# ProPrj__B__2024-10-26.net
KiCad netlist of a schematic drawn in EasyEDA Pro
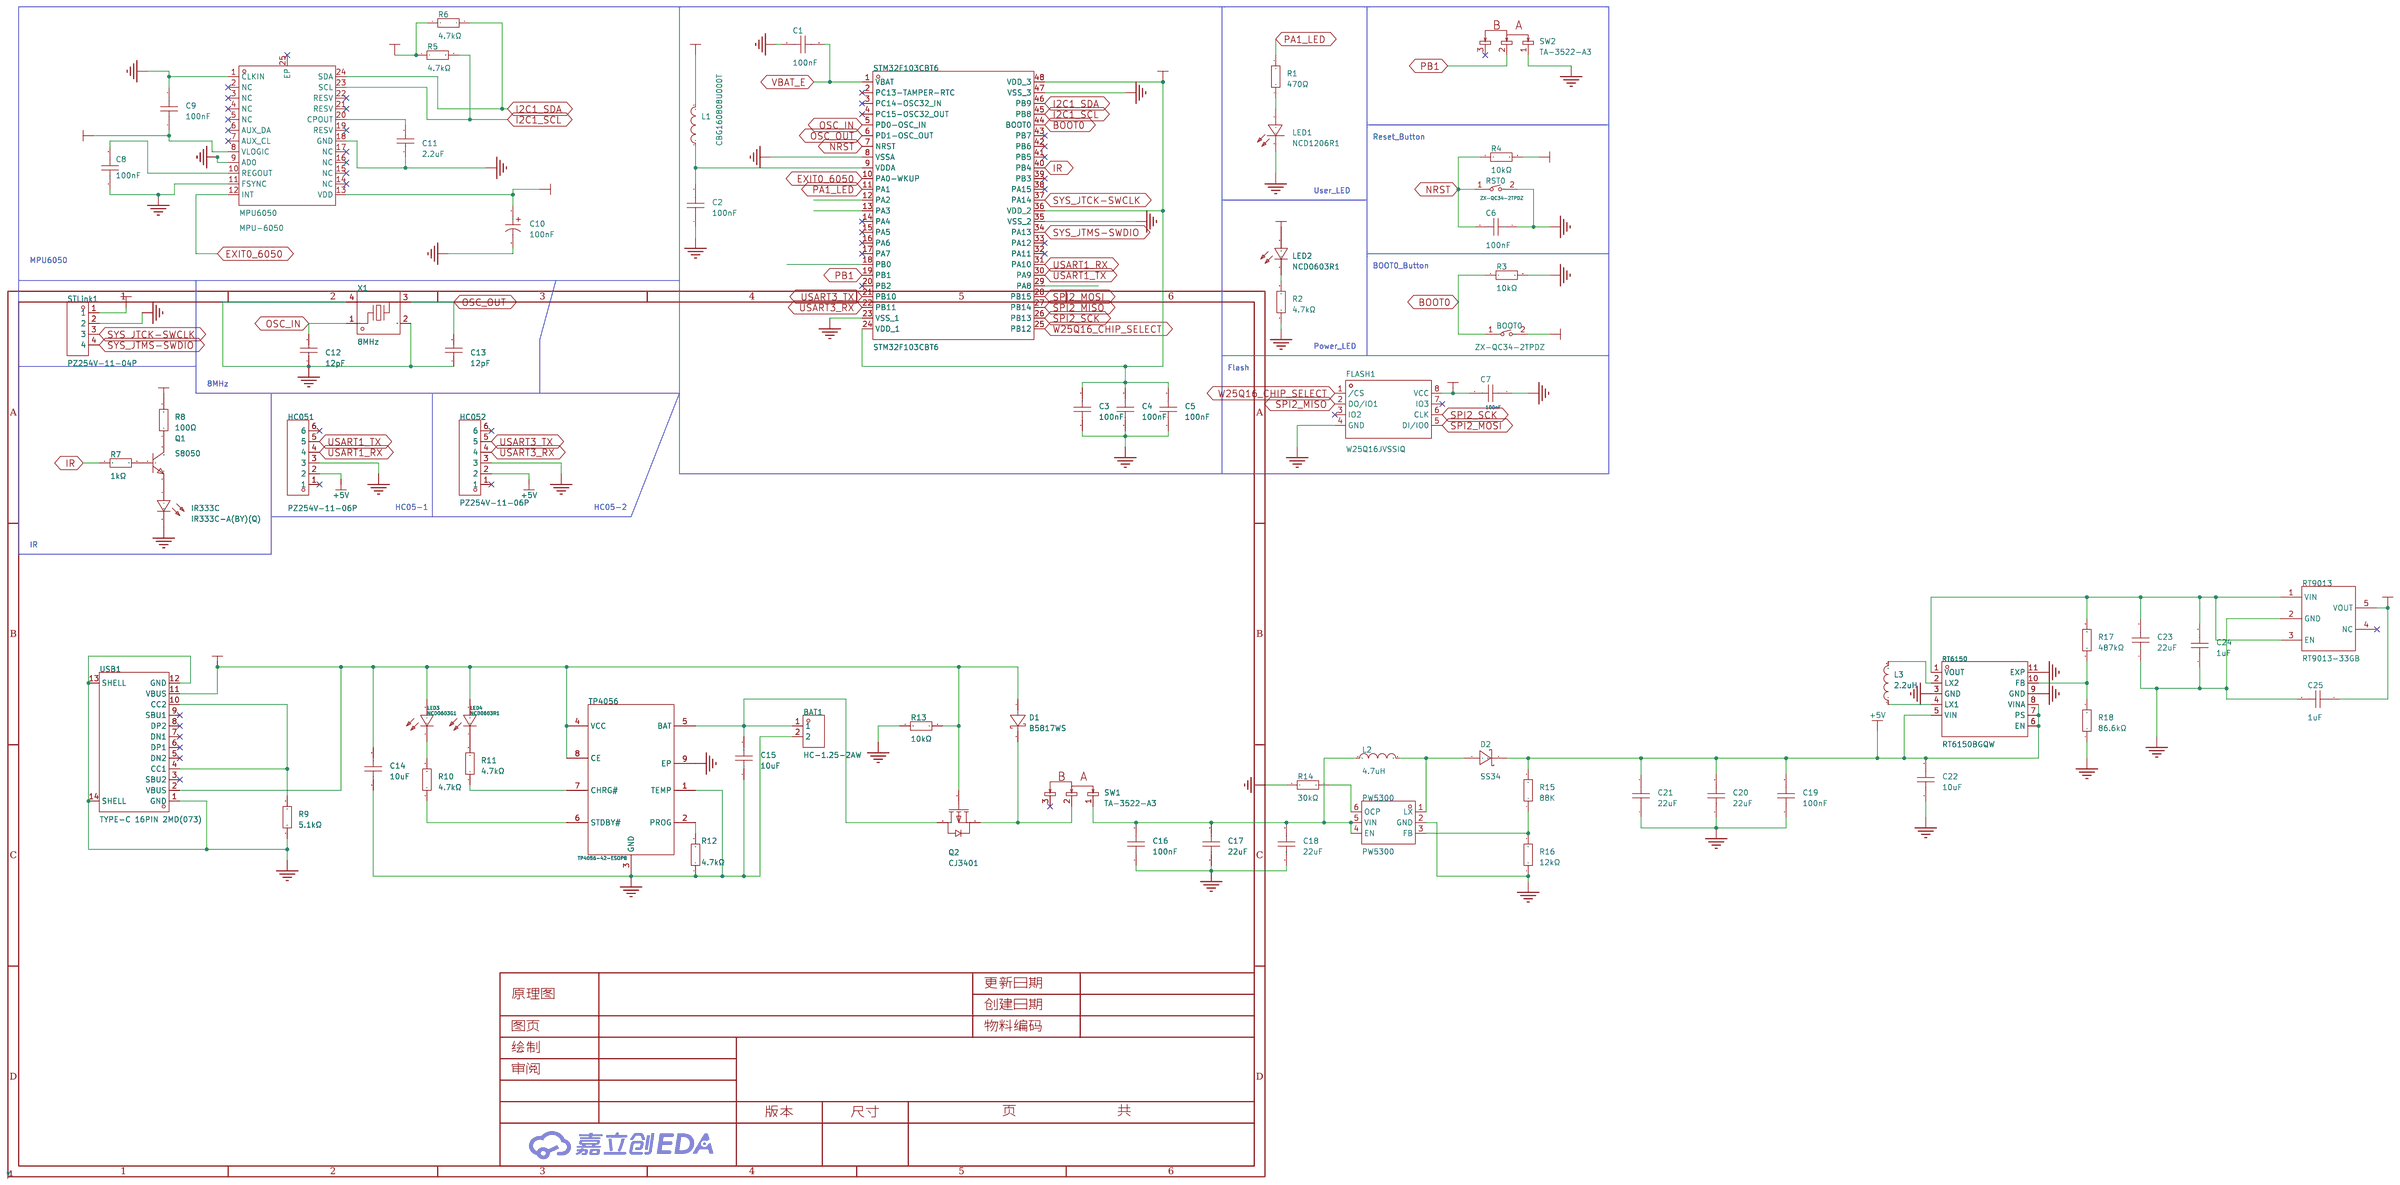
[diagram p0: schematic sheet]

(export (version "E")
  (design (tool "Eeschema 10.0.6"))
  (components
    (comp (ref "BAT1")
      (value "HC-1.25-2AW")
      (footprint "easyedapro:CONN-TH_2P-P1.25_HCTL_HC-1.25-2AW")
      (fields (field (name "Manufacturer") "HCTL(华灿天禄)"))
      (libsource (lib "easyedapro") (part "HC-1.25-2AW"))
    )
    (comp (ref "BOOT0")
      (value "ZX-QC34-2TPDZ")
      (footprint "easyedapro:KEY-SMD_L3.9-W3.0-LS5.0-EH")
      (fields (field (name "Manufacturer") "Megastar(兆星)"))
      (libsource (lib "easyedapro") (part "ZX-QC34-2TPDZ"))
    )
    (comp (ref "C1")
      (value "100nF")
      (footprint "easyedapro:C0603")
      (description "容值:100nF;精度:±10%;额定电压:50V;材质(温度系数):X7R;")
      (fields
        (field (name "Manufacturer Part") "CC0603KRX7R9BB104")
        (field (name "Manufacturer") "YAGEO(国巨)")
      )
      (libsource (lib "easyedapro") (part "CC0603KRX7R9BB104"))
    )
    (comp (ref "C2")
      (value "100nF")
      (footprint "easyedapro:C0603")
      (description "容值:100nF;精度:±10%;额定电压:50V;材质(温度系数):X7R;")
      (fields
        (field (name "Manufacturer Part") "CC0603KRX7R9BB104")
        (field (name "Manufacturer") "YAGEO(国巨)")
      )
      (libsource (lib "easyedapro") (part "CC0603KRX7R9BB104"))
    )
    (comp (ref "C3")
      (value "100nF")
      (footprint "easyedapro:C0603")
      (description "容值:100nF;精度:±10%;额定电压:50V;材质(温度系数):X7R;")
      (fields
        (field (name "Manufacturer Part") "CC0603KRX7R9BB104")
        (field (name "Manufacturer") "YAGEO(国巨)")
      )
      (libsource (lib "easyedapro") (part "CC0603KRX7R9BB104"))
    )
    (comp (ref "C4")
      (value "100nF")
      (footprint "easyedapro:C0603")
      (description "容值:100nF;精度:±10%;额定电压:50V;材质(温度系数):X7R;")
      (fields
        (field (name "Manufacturer Part") "CC0603KRX7R9BB104")
        (field (name "Manufacturer") "YAGEO(国巨)")
      )
      (libsource (lib "easyedapro") (part "CC0603KRX7R9BB104"))
    )
    (comp (ref "C5")
      (value "100nF")
      (footprint "easyedapro:C0603")
      (description "容值:100nF;精度:±10%;额定电压:50V;材质(温度系数):X7R;")
      (fields
        (field (name "Manufacturer Part") "CC0603KRX7R9BB104")
        (field (name "Manufacturer") "YAGEO(国巨)")
      )
      (libsource (lib "easyedapro") (part "CC0603KRX7R9BB104"))
    )
    (comp (ref "C6")
      (value "100nF")
      (footprint "easyedapro:C0603")
      (description "容值:100nF;精度:±10%;额定电压:50V;材质(温度系数):X7R;")
      (fields
        (field (name "Manufacturer Part") "CC0603KRX7R9BB104")
        (field (name "Manufacturer") "YAGEO(国巨)")
      )
      (libsource (lib "easyedapro") (part "CC0603KRX7R9BB104"))
    )
    (comp (ref "C7")
      (value "100nF")
      (footprint "easyedapro:C0603")
      (description "容值:100nF;精度:±10%;额定电压:50V;材质(温度系数):X7R;")
      (fields
        (field (name "Manufacturer Part") "CC0603KRX7R9BB104")
        (field (name "Manufacturer") "YAGEO(国巨)")
      )
      (libsource (lib "easyedapro") (part "CC0603KRX7R9BB104"))
    )
    (comp (ref "C8")
      (value "100nF")
      (footprint "easyedapro:C0603")
      (description "容值:100nF;精度:±10%;额定电压:50V;材质(温度系数):X7R;")
      (fields
        (field (name "Manufacturer Part") "CC0603KRX7R9BB104")
        (field (name "Manufacturer") "YAGEO(国巨)")
      )
      (libsource (lib "easyedapro") (part "CC0603KRX7R9BB104"))
    )
    (comp (ref "C9")
      (value "100nF")
      (footprint "easyedapro:C0603")
      (description "容值:100nF;精度:±10%;额定电压:50V;材质(温度系数):X7R;")
      (fields
        (field (name "Manufacturer Part") "CC0603KRX7R9BB104")
        (field (name "Manufacturer") "YAGEO(国巨)")
      )
      (libsource (lib "easyedapro") (part "CC0603KRX7R9BB104"))
    )
    (comp (ref "C10")
      (value "100nF")
      (footprint "easyedapro:CAP-SMD_L3.2-W1.6-FD")
      (description "容值:100nF;精度:±20%;额定电压:50V;等效串联电阻:20Ω;")
      (fields (field (name "Manufacturer Part") "T491A104M050AT") (field (name "Manufacturer") "KEMET(基美)"))
      (libsource (lib "easyedapro") (part "T491A104M050AT"))
    )
    (comp (ref "C11")
      (value "2.2uF")
      (footprint "easyedapro:C0603")
      (description "容值:2.2uF;精度:±10%;额定电压:16V;材质(温度系数):X5R;")
      (fields
        (field (name "Manufacturer Part") "CL10A225KO8NNNC")
        (field (name "Manufacturer") "SAMSUNG(三星)")
      )
      (libsource (lib "easyedapro") (part "CL10A225KO8NNNC"))
    )
    (comp (ref "C12")
      (value "12pF")
      (footprint "easyedapro:C0603")
      (description "容值:12pF;精度:±5%;额定电压:50V;材质(温度系数):C0G;")
      (fields
        (field (name "Manufacturer Part") "CL10C120JB8NNNC")
        (field (name "Manufacturer") "SAMSUNG(三星)")
      )
      (libsource (lib "easyedapro") (part "CL10C120JB8NNNC"))
    )
    (comp (ref "C13")
      (value "12pF")
      (footprint "easyedapro:C0603")
      (description "容值:12pF;精度:±5%;额定电压:50V;材质(温度系数):C0G;")
      (fields
        (field (name "Manufacturer Part") "CL10C120JB8NNNC")
        (field (name "Manufacturer") "SAMSUNG(三星)")
      )
      (libsource (lib "easyedapro") (part "CL10C120JB8NNNC"))
    )
    (comp (ref "C14")
      (value "10uF")
      (footprint "easyedapro:C0603")
      (description "容值:10uF;精度:±20%;额定电压:16V;材质(温度系数):X5R;")
      (fields
        (field (name "Manufacturer Part") "HGC0603R5106M160NTHJ")
        (field (name "Manufacturer") "Chinocera(华瓷)")
      )
      (libsource (lib "easyedapro") (part "HGC0603R5106M160NTHJ"))
    )
    (comp (ref "C15")
      (value "10uF")
      (footprint "easyedapro:C0603")
      (description "容值:10uF;精度:±20%;额定电压:16V;材质(温度系数):X5R;")
      (fields
        (field (name "Manufacturer Part") "HGC0603R5106M160NTHJ")
        (field (name "Manufacturer") "Chinocera(华瓷)")
      )
      (libsource (lib "easyedapro") (part "HGC0603R5106M160NTHJ"))
    )
    (comp (ref "C16")
      (value "100nF")
      (footprint "easyedapro:C0603")
      (description "容值:100nF;精度:±10%;额定电压:50V;材质(温度系数):X7R;")
      (fields
        (field (name "Manufacturer Part") "CGA0603X7R104K500JT")
        (field (name "Manufacturer") "HRE(芯声)")
      )
      (libsource (lib "easyedapro") (part "cga0603x7r104k500jt"))
    )
    (comp (ref "C17")
      (value "22uF")
      (footprint "easyedapro:C0805")
      (description "容值:22uF;精度:±20%;额定电压:35V;材质(温度系数):X5R;")
      (fields
        (field (name "Manufacturer Part") "CGA0805X5R226M350MT")
        (field (name "Manufacturer") "HRE(芯声)")
      )
      (libsource (lib "easyedapro") (part "CGA0805X5R226M350MT"))
    )
    (comp (ref "C18")
      (value "22uF")
      (footprint "easyedapro:C0805")
      (description "容值:22uF;精度:±20%;额定电压:35V;材质(温度系数):X5R;")
      (fields
        (field (name "Manufacturer Part") "CGA0805X5R226M350MT")
        (field (name "Manufacturer") "HRE(芯声)")
      )
      (libsource (lib "easyedapro") (part "CGA0805X5R226M350MT"))
    )
    (comp (ref "C19")
      (value "100nF")
      (footprint "easyedapro:C0603")
      (description "容值:100nF;精度:±10%;额定电压:50V;材质(温度系数):X7R;")
      (fields
        (field (name "Manufacturer Part") "CGA0603X7R104K500JT")
        (field (name "Manufacturer") "HRE(芯声)")
      )
      (libsource (lib "easyedapro") (part "cga0603x7r104k500jt"))
    )
    (comp (ref "C20")
      (value "22uF")
      (footprint "easyedapro:C0805")
      (description "容值:22uF;精度:±20%;额定电压:35V;材质(温度系数):X5R;")
      (fields
        (field (name "Manufacturer Part") "CGA0805X5R226M350MT")
        (field (name "Manufacturer") "HRE(芯声)")
      )
      (libsource (lib "easyedapro") (part "CGA0805X5R226M350MT"))
    )
    (comp (ref "C21")
      (value "22uF")
      (footprint "easyedapro:C0805")
      (description "容值:22uF;精度:±20%;额定电压:35V;材质(温度系数):X5R;")
      (fields
        (field (name "Manufacturer Part") "CGA0805X5R226M350MT")
        (field (name "Manufacturer") "HRE(芯声)")
      )
      (libsource (lib "easyedapro") (part "CGA0805X5R226M350MT"))
    )
    (comp (ref "C22")
      (value "10uF")
      (footprint "easyedapro:C0603")
      (description "容值:10uF;精度:±20%;额定电压:16V;材质(温度系数):X5R;")
      (fields
        (field (name "Manufacturer Part") "HGC0603R5106M160NTHJ")
        (field (name "Manufacturer") "Chinocera(华瓷)")
      )
      (libsource (lib "easyedapro") (part "HGC0603R5106M160NTHJ"))
    )
    (comp (ref "C23")
      (value "22uF")
      (footprint "easyedapro:C0603")
      (description "容值:22uF;精度:±20%;额定电压:16V;材质(温度系数):X5R;")
      (fields
        (field (name "Manufacturer Part") "CGA0603X5R226M160JT")
        (field (name "Manufacturer") "HRE(芯声)")
      )
      (libsource (lib "easyedapro") (part "CGA0603X5R226M160JT"))
    )
    (comp (ref "C24")
      (value "1uF")
      (footprint "easyedapro:C0603")
      (description "容值:1uF;精度:±10%;额定电压:16V;材质(温度系数):X5R;")
      (fields
        (field (name "Manufacturer Part") "CGA0603X5R105K160JT")
        (field (name "Manufacturer") "HRE(芯声)")
      )
      (libsource (lib "easyedapro") (part "CGA0603X5R105K160JT"))
    )
    (comp (ref "C25")
      (value "1uF")
      (footprint "easyedapro:C0603")
      (description "容值:1uF;精度:±10%;额定电压:16V;材质(温度系数):X5R;")
      (fields
        (field (name "Manufacturer Part") "CGA0603X5R105K160JT")
        (field (name "Manufacturer") "HRE(芯声)")
      )
      (libsource (lib "easyedapro") (part "CGA0603X5R105K160JT"))
    )
    (comp (ref "D1")
      (value "B5817WS")
      (footprint "easyedapro:SOD-323_L1.7-W1.3-LS2.5-FD")
      (description "二极管配置:独立式;正向压降(Vf):450mV@1.0A;直流反向耐压(Vr):20V;平均整流电流(Io):1A;")
      (fields (field (name "Manufacturer") "宏迦橙"))
      (libsource (lib "easyedapro") (part "B5817WS_C7420329"))
    )
    (comp (ref "D2")
      (value "SS34")
      (footprint "easyedapro:SMB_L4.6-W3.6-LS5.3-RD")
      (description "正向压降(Vf):500mV@3A;直流反向耐压(Vr):40V;平均整流电流(Io):3A;")
      (fields (field (name "Manufacturer") "BORN(伯恩半导体)"))
      (libsource (lib "easyedapro") (part "SS34_C266556"))
    )
    (comp (ref "FLASH1")
      (value "W25Q16JVSSIQ")
      (footprint "easyedapro:SOIC-8_L5.3-W5.3-P1.27-LS8.0-BL")
      (description "（与C82317为同一颗物料，只是编带方式不一样。）3V 16Mbit Serial Flash Memory with dual/quad SPI")
      (fields (field (name "Manufacturer") "WINBOND(华邦)"))
      (libsource (lib "easyedapro") (part "W25Q16JVSSIQTR"))
    )
    (comp (ref "HC051")
      (value "PZ254V-11-06P")
      (footprint "easyedapro:HDR-TH_6P-P2.54-V-M")
      (fields (field (name "Manufacturer") "XFCN(兴飞)"))
      (libsource (lib "easyedapro") (part "PZ254V-11-06P"))
    )
    (comp (ref "HC052")
      (value "PZ254V-11-06P")
      (footprint "easyedapro:HDR-TH_6P-P2.54-V-M")
      (fields (field (name "Manufacturer") "XFCN(兴飞)"))
      (libsource (lib "easyedapro") (part "PZ254V-11-06P"))
    )
    (comp (ref "IR333C")
      (value "IR333C-A(BY)(Q)")
      (footprint "easyedapro:LED-TH_BD5.0-P2.54-FD")
      (description "波长:940nm;")
      (fields (field (name "Manufacturer") "EVERLIGHT(亿光)"))
      (libsource (lib "easyedapro") (part "ir333c-a(by)(q)"))
    )
    (comp (ref "L1")
      (value "CBG160808U000T")
      (footprint "easyedapro:L0603")
      (description "标称阻抗@测试频率:0Ω@100MHz;直流电阻(RDC):100mΩ;")
      (fields (field (name "Manufacturer") "FH(风华)"))
      (libsource (lib "easyedapro") (part "CBG160808U000T"))
    )
    (comp (ref "L2")
      (value "4.7uH")
      (footprint "easyedapro:IND-SMD_L5.4-W5.2_FXL0530")
      (description "电感值:4.7uH;精度:±20%;额定电流:4.5A;饱和电流(Isat):5A;类型:一体成型电感;")
      (fields (field (name "Manufacturer Part") "FXL0530-4R7-M") (field (name "Manufacturer") "cjiang(长江微电)"))
      (libsource (lib "easyedapro") (part "FXL0530-4R7-M"))
    )
    (comp (ref "L3")
      (value "2.2uH")
      (footprint "easyedapro:IND-SMD_L2.5-W2.0_MHCHL2520")
      (description "电感值:2.2uH;精度:±20%;额定电流:3A;饱和电流(Isat):3.8A;类型:一体成型电感;")
      (fields
        (field (name "Manufacturer Part") "FTC252012S2R2MBCA")
        (field (name "Manufacturer") "cjiang(长江微电)")
      )
      (libsource (lib "easyedapro") (part "FTC252012S2R2MBCA"))
    )
    (comp (ref "LED1")
      (value "NCD1206R1")
      (footprint "easyedapro:LED1206-R-RD_RED")
      (fields (field (name "Manufacturer") "国星光电"))
      (libsource (lib "easyedapro") (part "FC-3215HRK-620D"))
    )
    (comp (ref "LED2")
      (value "NCD0603R1")
      (footprint "easyedapro:LED0603-RD_RED")
      (fields (field (name "Manufacturer") "国星光电"))
      (libsource (lib "easyedapro") (part "FC-DA1608HRK-620D"))
    )
    (comp (ref "LED3")
      (value "NCD0603G1")
      (footprint "easyedapro:led0603-rd_1")
      (fields (field (name "Manufacturer") "国星光电"))
      (libsource (lib "easyedapro") (part "FC-D1608UGK-520D10"))
    )
    (comp (ref "LED4")
      (value "NCD0603R1")
      (footprint "easyedapro:led0603-rd_1")
      (fields (field (name "Manufacturer") "国星光电"))
      (libsource (lib "easyedapro") (part "FC-D1608UGK-520D10"))
    )
    (comp (ref "MPU6050")
      (value "MPU-6050")
      (footprint "easyedapro:QFN-24_L4.0-W4.0-P0.50-BL-EP2.7")
      (description "传感器类型:加速度计陀螺仪;")
      (fields (field (name "Manufacturer") "TDK InvenSense(应美盛)"))
      (libsource (lib "easyedapro") (part "MPU-6050_C24112"))
    )
    (comp (ref "PW5300")
      (value "PW5300")
      (footprint "easyedapro:SOT-23-6_L2.9-W1.6-P0.95-LS2.8-BL")
      (libsource (lib "easyedapro") (part "PW5300"))
    )
    (comp (ref "Q1")
      (value "S8050")
      (footprint "easyedapro:SOT-23-3_L2.9-W1.6-P1.90-LS2.8-BR")
      (description "晶体管类型:NPN;集电极电流(Ic):500mA;集射极击穿电压(Vceo):25V;功率(Pd):300mW;")
      (fields (field (name "Manufacturer") "Hottech(合科泰)"))
      (libsource (lib "easyedapro") (part "S8050_C181158"))
    )
    (comp (ref "Q2")
      (value "CJ3401")
      (footprint "easyedapro:SOT-23-3_L2.9-W1.6-P1.90-LS2.8-BR")
      (fields (field (name "Manufacturer") "CJ(江苏长电/长晶)"))
      (libsource (lib "easyedapro") (part "CJ3401"))
    )
    (comp (ref "R1")
      (value "470Ω")
      (footprint "easyedapro:R0603")
      (description "电阻类型:厚膜电阻;阻值:470Ω;精度:±1%;功率:100mW;最大工作电压:75V;温度系数:±100ppm/°C;")
      (fields
        (field (name "Manufacturer Part") "0603WAF4700T5E")
        (field (name "Manufacturer") "UNI-ROYAL(厚声)")
      )
      (libsource (lib "easyedapro") (part "0603WAF4700T5E"))
    )
    (comp (ref "R2")
      (value "4.7kΩ")
      (footprint "easyedapro:R0603")
      (description "电阻类型:厚膜电阻;阻值:4.7kΩ;精度:±1%;功率:100mW;最大工作电压:75V;温度系数:±100ppm/°C;")
      (fields
        (field (name "Manufacturer Part") "0603WAF4701T5E")
        (field (name "Manufacturer") "UNI-ROYAL(厚声)")
      )
      (libsource (lib "easyedapro") (part "0603WAF4701T5E"))
    )
    (comp (ref "R3")
      (value "10kΩ")
      (footprint "easyedapro:R0603")
      (description "电阻类型:厚膜电阻;阻值:10kΩ;精度:±1%;功率:100mW;最大工作电压:75V;温度系数:±100ppm/°C;")
      (fields
        (field (name "Manufacturer Part") "0603WAF1002T5E")
        (field (name "Manufacturer") "UNI-ROYAL(厚声)")
      )
      (libsource (lib "easyedapro") (part "0603WAF1002T5E"))
    )
    (comp (ref "R4")
      (value "10kΩ")
      (footprint "easyedapro:R0603")
      (description "电阻类型:厚膜电阻;阻值:10kΩ;精度:±1%;功率:100mW;最大工作电压:75V;温度系数:±100ppm/°C;")
      (fields
        (field (name "Manufacturer Part") "0603WAF1002T5E")
        (field (name "Manufacturer") "UNI-ROYAL(厚声)")
      )
      (libsource (lib "easyedapro") (part "0603WAF1002T5E"))
    )
    (comp (ref "R5")
      (value "4.7kΩ")
      (footprint "easyedapro:R0603")
      (description "电阻类型:厚膜电阻;阻值:4.7kΩ;精度:±1%;功率:100mW;最大工作电压:75V;温度系数:±100ppm/°C;")
      (fields
        (field (name "Manufacturer Part") "0603WAF4701T5E")
        (field (name "Manufacturer") "UNI-ROYAL(厚声)")
      )
      (libsource (lib "easyedapro") (part "0603WAF4701T5E"))
    )
    (comp (ref "R6")
      (value "4.7kΩ")
      (footprint "easyedapro:R0603")
      (description "电阻类型:厚膜电阻;阻值:4.7kΩ;精度:±1%;功率:100mW;最大工作电压:75V;温度系数:±100ppm/°C;")
      (fields
        (field (name "Manufacturer Part") "0603WAF4701T5E")
        (field (name "Manufacturer") "UNI-ROYAL(厚声)")
      )
      (libsource (lib "easyedapro") (part "0603WAF4701T5E"))
    )
    (comp (ref "R7")
      (value "1kΩ")
      (footprint "easyedapro:R0603")
      (description "电阻类型:厚膜电阻;阻值:1kΩ;精度:±1%;功率:100mW;最大工作电压:75V;温度系数:±100ppm/°C;")
      (fields
        (field (name "Manufacturer Part") "0603WAF1001T5E")
        (field (name "Manufacturer") "UNI-ROYAL(厚声)")
      )
      (libsource (lib "easyedapro") (part "0603WAF1001T5E"))
    )
    (comp (ref "R8")
      (value "100Ω")
      (footprint "easyedapro:R0603")
      (description "电阻类型:厚膜电阻;阻值:100Ω;精度:±1%;功率:100mW;最大工作电压:75V;温度系数:±200ppm/°C;")
      (fields
        (field (name "Manufacturer Part") "0603WAF1000T5E")
        (field (name "Manufacturer") "UNI-ROYAL(厚声)")
      )
      (libsource (lib "easyedapro") (part "0603WAF1000T5E"))
    )
    (comp (ref "R9")
      (value "5.1kΩ")
      (footprint "easyedapro:R0603")
      (description "电阻类型:厚膜电阻;阻值:5.1kΩ;精度:±1%;功率:100mW;最大工作电压:75V;温度系数:±100ppm/°C;")
      (fields
        (field (name "Manufacturer Part") "0603WAF5101T5E")
        (field (name "Manufacturer") "UNI-ROYAL(厚声)")
      )
      (libsource (lib "easyedapro") (part "0603WAF5101T5E"))
    )
    (comp (ref "R10")
      (value "4.7kΩ")
      (footprint "easyedapro:R0603")
      (description "电阻类型:厚膜电阻;阻值:4.7kΩ;精度:±1%;功率:100mW;最大工作电压:75V;温度系数:±100ppm/°C;")
      (fields
        (field (name "Manufacturer Part") "0603WAF4701T5E")
        (field (name "Manufacturer") "UNI-ROYAL(厚声)")
      )
      (libsource (lib "easyedapro") (part "0603WAF4701T5E"))
    )
    (comp (ref "R11")
      (value "4.7kΩ")
      (footprint "easyedapro:R0603")
      (description "电阻类型:厚膜电阻;阻值:4.7kΩ;精度:±1%;功率:100mW;最大工作电压:75V;温度系数:±100ppm/°C;")
      (fields
        (field (name "Manufacturer Part") "0603WAF4701T5E")
        (field (name "Manufacturer") "UNI-ROYAL(厚声)")
      )
      (libsource (lib "easyedapro") (part "0603WAF4701T5E"))
    )
    (comp (ref "R12")
      (value "4.7kΩ")
      (footprint "easyedapro:R0603")
      (description "电阻类型:厚膜电阻;阻值:4.7kΩ;精度:±1%;功率:100mW;最大工作电压:75V;温度系数:±100ppm/°C;")
      (fields
        (field (name "Manufacturer Part") "0603WAF4701T5E")
        (field (name "Manufacturer") "UNI-ROYAL(厚声)")
      )
      (libsource (lib "easyedapro") (part "0603WAF4701T5E"))
    )
    (comp (ref "R13")
      (value "10kΩ")
      (footprint "easyedapro:R0603")
      (description "电阻类型:厚膜电阻;阻值:10kΩ;精度:±1%;功率:100mW;最大工作电压:75V;温度系数:±100ppm/°C;")
      (fields
        (field (name "Manufacturer Part") "0603WAF1002T5E")
        (field (name "Manufacturer") "UNI-ROYAL(厚声)")
      )
      (libsource (lib "easyedapro") (part "0603WAF1002T5E"))
    )
    (comp (ref "R14")
      (value "30kΩ")
      (footprint "easyedapro:R0603")
      (description "电阻类型:厚膜电阻;阻值:30kΩ;精度:±1%;功率:100mW;最大工作电压:75V;温度系数:±100ppm/°C;")
      (fields
        (field (name "Manufacturer Part") "0603WAF3002T5E")
        (field (name "Manufacturer") "UNI-ROYAL(厚声)")
      )
      (libsource (lib "easyedapro") (part "0603WAF3002T5E"))
    )
    (comp (ref "R15") (value "88K") (footprint "easyedapro:R0603") (libsource (lib "easyedapro") (part "电阻")))
    (comp (ref "R16")
      (value "12kΩ")
      (footprint "easyedapro:R0603")
      (description "电阻类型:厚膜电阻;阻值:12kΩ;精度:±1%;功率:100mW;最大工作电压:75V;温度系数:±100ppm/°C;")
      (fields
        (field (name "Manufacturer Part") "0603WAF1202T5E")
        (field (name "Manufacturer") "UNI-ROYAL(厚声)")
      )
      (libsource (lib "easyedapro") (part "0603WAF1202T5E"))
    )
    (comp (ref "R17")
      (value "487kΩ")
      (footprint "easyedapro:R0603")
      (description "电阻类型:厚膜电阻;阻值:487kΩ;精度:±1%;功率:100mW;最大工作电压:75V;温度系数:±100ppm/°C;")
      (fields
        (field (name "Manufacturer Part") "0603WAF4873T5E")
        (field (name "Manufacturer") "UNI-ROYAL(厚声)")
      )
      (libsource (lib "easyedapro") (part "0603WAF4873T5E"))
    )
    (comp (ref "R18")
      (value "86.6kΩ")
      (footprint "easyedapro:R0603")
      (description "电阻类型:厚膜电阻;阻值:86.6kΩ;精度:±1%;功率:100mW;最大工作电压:75V;温度系数:±100ppm/°C;")
      (fields
        (field (name "Manufacturer Part") "0603WAF8662T5E")
        (field (name "Manufacturer") "UNI-ROYAL(厚声)")
      )
      (libsource (lib "easyedapro") (part "0603WAF8662T5E"))
    )
    (comp (ref "RST0")
      (value "ZX-QC34-2TPDZ")
      (footprint "easyedapro:KEY-SMD_L3.9-W3.0-LS5.0-EH")
      (fields (field (name "Manufacturer") "Megastar(兆星)"))
      (libsource (lib "easyedapro") (part "ZX-QC34-2TPDZ"))
    )
    (comp (ref "RT6150")
      (value "RT6150BGQW")
      (footprint "easyedapro:WSON-10_L2.5-W2.5-P0.50-BL-EP")
      (description "功能类型:升降压型;输入电压:1.8V~5.5V;输出电压:1.8V~5.5V;输出电流(最大值):800mA;")
      (fields (field (name "Manufacturer") "RICHTEK(立锜)"))
      (libsource (lib "easyedapro") (part "RT6150BGQW"))
    )
    (comp (ref "RT9013")
      (value "RT9013-33GB")
      (footprint "easyedapro:SOT-23-5_L3.0-W1.7-P0.95-LS2.8-BL")
      (description "输出类型:固定;最大输入电压:5.5V;输出电压:3.3V;最大输出电流:500mA;电源纹波抑制比(PSRR):50dB@(10kHz);输出极性:正极;")
      (fields (field (name "Manufacturer") "RICHTEK(立锜)"))
      (libsource (lib "easyedapro") (part "RT9013-33GB"))
    )
    (comp (ref "STLink1")
      (value "PZ254V-11-04P")
      (footprint "easyedapro:HDR-TH_4P-P2.54-V-M")
      (fields (field (name "Manufacturer") "XFCN(兴飞)"))
      (libsource (lib "easyedapro") (part "PZ254V-11-04P_C2691448"))
    )
    (comp (ref "STM32F103CBT6")
      (value "STM32F103CBT6")
      (fields (field (name "Manufacturer") "ST(意法半导体)"))
      (libsource (lib "easyedapro") (part "APM32F103CBT6"))
    )
    (comp (ref "SW1")
      (value "TA-3522-A3")
      (footprint "easyedapro:SW-TH_3P-L9.1-W3.5-P2.50-A3")
      (fields (field (name "Manufacturer") "Yuandi(元迪)"))
      (libsource (lib "easyedapro") (part "TA-3522-A3"))
    )
    (comp (ref "SW2")
      (value "TA-3522-A3")
      (footprint "easyedapro:SW-TH_3P-L9.1-W3.5-P2.50-A3")
      (fields (field (name "Manufacturer") "Yuandi(元迪)"))
      (libsource (lib "easyedapro") (part "TA-3522-A3"))
    )
    (comp (ref "TP4056")
      (value "TP4056-42-ESOP8")
      (footprint "easyedapro:ESOP-8_L4.9-W3.9-P1.27-LS6.0-BL-EP")
      (description "锂电池充电芯片 42代表电池满电电压4.2V。")
      (fields (field (name "Manufacturer") "TOPPOWER(南京拓微)"))
      (libsource (lib "easyedapro") (part "TP4056"))
    )
    (comp (ref "USB1")
      (value "TYPE-C 16PIN 2MD(073)")
      (footprint "easyedapro:USB-C-SMD_TYPE-C-6PIN-2MD-073")
      (description "连接器类型:Type-C;标准:USB 3.1;公母:母;安装方式:卧贴;触点数量:16P;端口数量:1;额定电流 - 电源:5A;工作温度范围:-25°C~+85°C;")
      (fields (field (name "Manufacturer") "SHOU HAN(首韩)"))
      (libsource (lib "easyedapro") (part "TYPE-C 16PIN 2MD(073)"))
    )
    (comp (ref "X1")
      (value "8MHz")
      (footprint "easyedapro:OSC-SMD_4P-L3.2-W2.5-BL")
      (description "晶振类型:贴片晶振;频率:8MHz;常温频差:±10ppm;外接负载电容:12pF;频率稳定度(全温):±20ppm;")
      (fields (field (name "Manufacturer Part") "X32258MOB4SI") (field (name "Manufacturer") "YXC(扬兴晶振)"))
      (libsource (lib "easyedapro") (part "x32258mob4si"))
    )
  )
  (nets
    (net (code "1") (name "+5V") (class "Default")
      (node (ref "C19") (pin "2") (pinfunction "2_2") (pintype "unspecified"))
      (node (ref "C20") (pin "2") (pinfunction "2_2") (pintype "unspecified"))
      (node (ref "C21") (pin "2") (pinfunction "2_2") (pintype "unspecified"))
      (node (ref "C22") (pin "2") (pinfunction "2_2") (pintype "unspecified"))
      (node (ref "D2") (pin "1") (pinfunction "C_1") (pintype "unspecified"))
      (node (ref "HC051") (pin "2") (pinfunction "2_2") (pintype "unspecified"))
      (node (ref "HC052") (pin "2") (pinfunction "2_2") (pintype "unspecified"))
      (node (ref "R15") (pin "2") (pinfunction "2_2") (pintype "input"))
      (node (ref "RT6150") (pin "5") (pinfunction "VIN_5") (pintype "input"))
      (node (ref "RT6150") (pin "6") (pinfunction "EN_6") (pintype "input"))
      (node (ref "RT6150") (pin "7") (pinfunction "PS_7") (pintype "input"))
      (node (ref "RT6150") (pin "8") (pinfunction "VINA_8") (pintype "input"))
    )
    (net (code "2") (name "3V3") (class "Default")
      (node (ref "BOOT0") (pin "2") (pinfunction "2_2") (pintype "unspecified"))
      (node (ref "C10") (pin "1") (pinfunction "1_1") (pintype "input"))
      (node (ref "C25") (pin "1") (pinfunction "1_1") (pintype "unspecified"))
      (node (ref "C3") (pin "2") (pinfunction "2_2") (pintype "unspecified"))
      (node (ref "C4") (pin "2") (pinfunction "2_2") (pintype "unspecified"))
      (node (ref "C5") (pin "2") (pinfunction "2_2") (pintype "unspecified"))
      (node (ref "C7") (pin "2") (pinfunction "2_2") (pintype "unspecified"))
      (node (ref "C9") (pin "1") (pinfunction "1_1") (pintype "unspecified"))
      (node (ref "FLASH1") (pin "8") (pinfunction "VCC_8") (pintype "unspecified"))
      (node (ref "L1") (pin "2") (pinfunction "2_2") (pintype "unspecified"))
      (node (ref "LED2") (pin "2") (pinfunction "A_2") (pintype "input"))
      (node (ref "MPU6050") (pin "13") (pinfunction "VDD_13") (pintype "unspecified"))
      (node (ref "MPU6050") (pin "8") (pinfunction "VLOGIC_8") (pintype "unspecified"))
      (node (ref "R4") (pin "2") (pinfunction "2_2") (pintype "input"))
      (node (ref "R5") (pin "1") (pinfunction "1_1") (pintype "input"))
      (node (ref "R6") (pin "1") (pinfunction "1_1") (pintype "input"))
      (node (ref "R8") (pin "2") (pinfunction "2_2") (pintype "input"))
      (node (ref "RT9013") (pin "5") (pinfunction "VOUT_5") (pintype "unspecified"))
      (node (ref "STLink1") (pin "1") (pinfunction "1_1") (pintype "unspecified"))
      (node (ref "STM32F103CBT6") (pin "24") (pinfunction "VDD_1_24") (pintype "unspecified"))
      (node (ref "STM32F103CBT6") (pin "36") (pinfunction "VDD_2_36") (pintype "unspecified"))
      (node (ref "STM32F103CBT6") (pin "48") (pinfunction "VDD_3_48") (pintype "unspecified"))
    )
    (net (code "3") (name "BOOT0") (class "Default")
      (node (ref "BOOT0") (pin "1") (pinfunction "1_1") (pintype "unspecified"))
      (node (ref "R3") (pin "1") (pinfunction "1_1") (pintype "input"))
      (node (ref "STM32F103CBT6") (pin "44") (pinfunction "BOOT0_44") (pintype "unspecified"))
    )
    (net (code "4") (name "EXIT0_6050") (class "Default")
      (node (ref "MPU6050") (pin "12") (pinfunction "INT_12") (pintype "unspecified"))
      (node (ref "STM32F103CBT6") (pin "10") (pinfunction "PA0-WKUP_10") (pintype "unspecified"))
    )
    (net (code "5") (name "GND") (class "Default")
      (node (ref "BAT1") (pin "2") (pinfunction "2_2") (pintype "unspecified"))
      (node (ref "C1") (pin "1") (pinfunction "1_1") (pintype "unspecified"))
      (node (ref "C10") (pin "2") (pinfunction "2_2") (pintype "input"))
      (node (ref "C11") (pin "1") (pinfunction "1_1") (pintype "input"))
      (node (ref "C12") (pin "1") (pinfunction "1_1") (pintype "input"))
      (node (ref "C13") (pin "1") (pinfunction "1_1") (pintype "input"))
      (node (ref "C14") (pin "1") (pinfunction "1_1") (pintype "unspecified"))
      (node (ref "C15") (pin "1") (pinfunction "1_1") (pintype "unspecified"))
      (node (ref "C16") (pin "1") (pinfunction "1_1") (pintype "unspecified"))
      (node (ref "C17") (pin "1") (pinfunction "1_1") (pintype "unspecified"))
      (node (ref "C18") (pin "1") (pinfunction "1_1") (pintype "unspecified"))
      (node (ref "C19") (pin "1") (pinfunction "1_1") (pintype "unspecified"))
      (node (ref "C2") (pin "1") (pinfunction "1_1") (pintype "unspecified"))
      (node (ref "C20") (pin "1") (pinfunction "1_1") (pintype "unspecified"))
      (node (ref "C21") (pin "1") (pinfunction "1_1") (pintype "unspecified"))
      (node (ref "C22") (pin "1") (pinfunction "1_1") (pintype "unspecified"))
      (node (ref "C23") (pin "1") (pinfunction "1_1") (pintype "unspecified"))
      (node (ref "C24") (pin "1") (pinfunction "1_1") (pintype "unspecified"))
      (node (ref "C25") (pin "2") (pinfunction "2_2") (pintype "unspecified"))
      (node (ref "C3") (pin "1") (pinfunction "1_1") (pintype "unspecified"))
      (node (ref "C4") (pin "1") (pinfunction "1_1") (pintype "unspecified"))
      (node (ref "C5") (pin "1") (pinfunction "1_1") (pintype "unspecified"))
      (node (ref "C6") (pin "1") (pinfunction "1_1") (pintype "unspecified"))
      (node (ref "C7") (pin "1") (pinfunction "1_1") (pintype "unspecified"))
      (node (ref "C8") (pin "1") (pinfunction "1_1") (pintype "unspecified"))
      (node (ref "C9") (pin "2") (pinfunction "2_2") (pintype "unspecified"))
      (node (ref "FLASH1") (pin "4") (pinfunction "GND_4") (pintype "unspecified"))
      (node (ref "HC051") (pin "3") (pinfunction "3_3") (pintype "unspecified"))
      (node (ref "HC052") (pin "3") (pinfunction "3_3") (pintype "unspecified"))
      (node (ref "IR333C") (pin "2") (pinfunction "C_2") (pintype "input"))
      (node (ref "LED1") (pin "2") (pinfunction "K_2") (pintype "unspecified"))
      (node (ref "MPU6050") (pin "1") (pinfunction "CLKIN_1") (pintype "unspecified"))
      (node (ref "MPU6050") (pin "11") (pinfunction "FSYNC_11") (pintype "unspecified"))
      (node (ref "MPU6050") (pin "18") (pinfunction "GND_18") (pintype "unspecified"))
      (node (ref "MPU6050") (pin "9") (pinfunction "AD0_9") (pintype "unspecified"))
      (node (ref "PW5300") (pin "2") (pinfunction "GND_2") (pintype "unspecified"))
      (node (ref "R12") (pin "1") (pinfunction "1_1") (pintype "input"))
      (node (ref "R13") (pin "1") (pinfunction "1_1") (pintype "input"))
      (node (ref "R14") (pin "1") (pinfunction "1_1") (pintype "input"))
      (node (ref "R16") (pin "1") (pinfunction "1_1") (pintype "input"))
      (node (ref "R18") (pin "1") (pinfunction "1_1") (pintype "input"))
      (node (ref "R2") (pin "1") (pinfunction "1_1") (pintype "input"))
      (node (ref "R3") (pin "2") (pinfunction "2_2") (pintype "input"))
      (node (ref "R9") (pin "1") (pinfunction "1_1") (pintype "input"))
      (node (ref "RST0") (pin "2") (pinfunction "2_2") (pintype "unspecified"))
      (node (ref "RT6150") (pin "11") (pinfunction "EXP_11") (pintype "input"))
      (node (ref "RT6150") (pin "3") (pinfunction "GND_3") (pintype "input"))
      (node (ref "RT6150") (pin "9") (pinfunction "GND_9") (pintype "input"))
      (node (ref "RT9013") (pin "2") (pinfunction "GND_2") (pintype "unspecified"))
      (node (ref "STLink1") (pin "2") (pinfunction "2_2") (pintype "unspecified"))
      (node (ref "STM32F103CBT6") (pin "23") (pinfunction "VSS_1_23") (pintype "unspecified"))
      (node (ref "STM32F103CBT6") (pin "35") (pinfunction "VSS_2_35") (pintype "unspecified"))
      (node (ref "STM32F103CBT6") (pin "47") (pinfunction "VSS_3_47") (pintype "unspecified"))
      (node (ref "STM32F103CBT6") (pin "8") (pinfunction "VSSA_8") (pintype "unspecified"))
      (node (ref "SW2") (pin "1") (pinfunction "1_1") (pintype "unspecified"))
      (node (ref "TP4056") (pin "1") (pinfunction "TEMP_1") (pintype "unspecified"))
      (node (ref "TP4056") (pin "3") (pinfunction "GND_3") (pintype "unspecified"))
      (node (ref "TP4056") (pin "9") (pinfunction "EP_9") (pintype "unspecified"))
      (node (ref "USB1") (pin "1") (pinfunction "GND_1") (pintype "unspecified"))
      (node (ref "USB1") (pin "12") (pinfunction "GND_12") (pintype "unspecified"))
      (node (ref "USB1") (pin "13") (pinfunction "SHELL_13") (pintype "unspecified"))
      (node (ref "USB1") (pin "14") (pinfunction "SHELL_14") (pintype "unspecified"))
      (node (ref "X1") (pin "2") (pinfunction "GND_2") (pintype "input"))
      (node (ref "X1") (pin "4") (pinfunction "GND_4") (pintype "input"))
    )
    (net (code "6") (name "I2C1_SCL") (class "Default")
      (node (ref "MPU6050") (pin "23") (pinfunction "SCL_23") (pintype "unspecified"))
      (node (ref "R5") (pin "2") (pinfunction "2_2") (pintype "input"))
      (node (ref "STM32F103CBT6") (pin "45") (pinfunction "PB8_45") (pintype "unspecified"))
    )
    (net (code "7") (name "I2C1_SDA") (class "Default")
      (node (ref "MPU6050") (pin "24") (pinfunction "SDA_24") (pintype "unspecified"))
      (node (ref "R6") (pin "2") (pinfunction "2_2") (pintype "input"))
      (node (ref "STM32F103CBT6") (pin "46") (pinfunction "PB9_46") (pintype "unspecified"))
    )
    (net (code "8") (name "IR") (class "Default")
      (node (ref "R7") (pin "1") (pinfunction "1_1") (pintype "input"))
      (node (ref "STM32F103CBT6") (pin "40") (pinfunction "PB4_40") (pintype "unspecified"))
    )
    (net (code "9") (name "NRST") (class "Default")
      (node (ref "C6") (pin "2") (pinfunction "2_2") (pintype "unspecified"))
      (node (ref "R4") (pin "1") (pinfunction "1_1") (pintype "input"))
      (node (ref "RST0") (pin "1") (pinfunction "1_1") (pintype "unspecified"))
      (node (ref "STM32F103CBT6") (pin "7") (pinfunction "NRST_7") (pintype "unspecified"))
    )
    (net (code "10") (name "Net-(D1-K)") (class "Default")
      (node (ref "D1") (pin "2") (pinfunction "K_2") (pintype "unspecified"))
      (node (ref "Q2") (pin "2") (pinfunction "S_2") (pintype "unspecified"))
      (node (ref "SW1") (pin "2") (pinfunction "2_2") (pintype "unspecified"))
    )
    (net (code "11") (name "Net-(D2-A)") (class "Default")
      (node (ref "D2") (pin "2") (pinfunction "A_2") (pintype "unspecified"))
      (node (ref "L2") (pin "2") (pinfunction "2_2") (pintype "unspecified"))
      (node (ref "PW5300") (pin "1") (pinfunction "LX_1") (pintype "unspecified"))
    )
    (net (code "12") (name "Net-(IR333C-A)") (class "Default")
      (node (ref "IR333C") (pin "1") (pinfunction "A_1") (pintype "input"))
      (node (ref "Q1") (pin "2") (pinfunction "2_2") (pintype "input"))
    )
    (net (code "13") (name "Net-(LED1-A)") (class "Default")
      (node (ref "LED1") (pin "1") (pinfunction "A_1") (pintype "unspecified"))
      (node (ref "R1") (pin "1") (pinfunction "1_1") (pintype "input"))
    )
    (net (code "14") (name "Net-(LED2-K)") (class "Default")
      (node (ref "LED2") (pin "1") (pinfunction "K_1") (pintype "input"))
      (node (ref "R2") (pin "2") (pinfunction "2_2") (pintype "input"))
    )
    (net (code "15") (name "Net-(LED3-K)") (class "Default")
      (node (ref "LED3") (pin "1") (pinfunction "K_1") (pintype "input"))
      (node (ref "R10") (pin "2") (pinfunction "2_2") (pintype "input"))
    )
    (net (code "16") (name "Net-(LED4-K)") (class "Default")
      (node (ref "LED4") (pin "1") (pinfunction "K_1") (pintype "input"))
      (node (ref "R11") (pin "2") (pinfunction "2_2") (pintype "input"))
    )
    (net (code "17") (name "Net-(MPU6050-CPOUT)") (class "Default")
      (node (ref "C11") (pin "2") (pinfunction "2_2") (pintype "input"))
      (node (ref "MPU6050") (pin "20") (pinfunction "CPOUT_20") (pintype "unspecified"))
    )
    (net (code "18") (name "Net-(MPU6050-REGOUT)") (class "Default")
      (node (ref "C8") (pin "2") (pinfunction "2_2") (pintype "unspecified"))
      (node (ref "MPU6050") (pin "10") (pinfunction "REGOUT_10") (pintype "unspecified"))
    )
    (net (code "19") (name "Net-(PW5300-EN)") (class "Default")
      (node (ref "C16") (pin "2") (pinfunction "2_2") (pintype "unspecified"))
      (node (ref "C17") (pin "2") (pinfunction "2_2") (pintype "unspecified"))
      (node (ref "C18") (pin "2") (pinfunction "2_2") (pintype "unspecified"))
      (node (ref "L2") (pin "1") (pinfunction "1_1") (pintype "unspecified"))
      (node (ref "PW5300") (pin "4") (pinfunction "EN_4") (pintype "unspecified"))
      (node (ref "PW5300") (pin "5") (pinfunction "VIN_5") (pintype "unspecified"))
      (node (ref "SW1") (pin "1") (pinfunction "1_1") (pintype "unspecified"))
    )
    (net (code "20") (name "Net-(PW5300-FB)") (class "Default")
      (node (ref "PW5300") (pin "3") (pinfunction "FB_3") (pintype "unspecified"))
      (node (ref "R15") (pin "1") (pinfunction "1_1") (pintype "input"))
      (node (ref "R16") (pin "2") (pinfunction "2_2") (pintype "input"))
    )
    (net (code "21") (name "Net-(PW5300-OCP)") (class "Default")
      (node (ref "PW5300") (pin "6") (pinfunction "OCP_6") (pintype "unspecified"))
      (node (ref "R14") (pin "2") (pinfunction "2_2") (pintype "input"))
    )
    (net (code "22") (name "Net-(Q1-Pad1)") (class "Default")
      (node (ref "Q1") (pin "1") (pinfunction "1_1") (pintype "input"))
      (node (ref "R7") (pin "2") (pinfunction "2_2") (pintype "input"))
    )
    (net (code "23") (name "Net-(Q1-Pad3)") (class "Default")
      (node (ref "Q1") (pin "3") (pinfunction "3_3") (pintype "input"))
      (node (ref "R8") (pin "1") (pinfunction "1_1") (pintype "input"))
    )
    (net (code "24") (name "Net-(Q2-D)") (class "Default")
      (node (ref "BAT1") (pin "1") (pinfunction "1_1") (pintype "unspecified"))
      (node (ref "C15") (pin "2") (pinfunction "2_2") (pintype "unspecified"))
      (node (ref "Q2") (pin "3") (pinfunction "D_3") (pintype "unspecified"))
      (node (ref "TP4056") (pin "5") (pinfunction "BAT_5") (pintype "unspecified"))
    )
    (net (code "25") (name "Net-(RT6150-FB)") (class "Default")
      (node (ref "R17") (pin "1") (pinfunction "1_1") (pintype "input"))
      (node (ref "R18") (pin "2") (pinfunction "2_2") (pintype "input"))
      (node (ref "RT6150") (pin "10") (pinfunction "FB_10") (pintype "input"))
    )
    (net (code "26") (name "Net-(RT6150-LX1)") (class "Default")
      (node (ref "L3") (pin "1") (pinfunction "1_1") (pintype "unspecified"))
      (node (ref "RT6150") (pin "4") (pinfunction "LX1_4") (pintype "input"))
    )
    (net (code "27") (name "Net-(RT6150-LX2)") (class "Default")
      (node (ref "L3") (pin "2") (pinfunction "2_2") (pintype "unspecified"))
      (node (ref "RT6150") (pin "2") (pinfunction "LX2_2") (pintype "input"))
    )
    (net (code "28") (name "Net-(RT6150-VOUT)") (class "Default")
      (node (ref "C23") (pin "2") (pinfunction "2_2") (pintype "unspecified"))
      (node (ref "C24") (pin "2") (pinfunction "2_2") (pintype "unspecified"))
      (node (ref "R17") (pin "2") (pinfunction "2_2") (pintype "input"))
      (node (ref "RT6150") (pin "1") (pinfunction "VOUT_1") (pintype "input"))
      (node (ref "RT9013") (pin "1") (pinfunction "VIN_1") (pintype "unspecified"))
      (node (ref "RT9013") (pin "3") (pinfunction "EN_3") (pintype "unspecified"))
    )
    (net (code "29") (name "Net-(STM32F103CBT6-VDDA)") (class "Default")
      (node (ref "C2") (pin "2") (pinfunction "2_2") (pintype "unspecified"))
      (node (ref "L1") (pin "1") (pinfunction "1_1") (pintype "unspecified"))
      (node (ref "STM32F103CBT6") (pin "9") (pinfunction "VDDA_9") (pintype "unspecified"))
    )
    (net (code "30") (name "Net-(TP4056-CHRG#)") (class "Default")
      (node (ref "R11") (pin "1") (pinfunction "1_1") (pintype "input"))
      (node (ref "TP4056") (pin "7") (pinfunction "CHRG#_7") (pintype "unspecified"))
    )
    (net (code "31") (name "Net-(TP4056-PROG)") (class "Default")
      (node (ref "R12") (pin "2") (pinfunction "2_2") (pintype "input"))
      (node (ref "TP4056") (pin "2") (pinfunction "PROG_2") (pintype "unspecified"))
    )
    (net (code "32") (name "Net-(TP4056-STDBY#)") (class "Default")
      (node (ref "R10") (pin "1") (pinfunction "1_1") (pintype "input"))
      (node (ref "TP4056") (pin "6") (pinfunction "STDBY#_6") (pintype "unspecified"))
    )
    (net (code "33") (name "Net-(USB1-CC1)") (class "Default")
      (node (ref "R9") (pin "2") (pinfunction "2_2") (pintype "input"))
      (node (ref "USB1") (pin "10") (pinfunction "CC2_10") (pintype "unspecified"))
      (node (ref "USB1") (pin "4") (pinfunction "CC1_4") (pintype "unspecified"))
    )
    (net (code "34") (name "OSC_IN") (class "Default")
      (node (ref "C12") (pin "2") (pinfunction "2_2") (pintype "input"))
      (node (ref "STM32F103CBT6") (pin "5") (pinfunction "PD0-OSC_IN_5") (pintype "unspecified"))
      (node (ref "X1") (pin "1") (pinfunction "1_1") (pintype "input"))
    )
    (net (code "35") (name "OSC_OUT") (class "Default")
      (node (ref "C13") (pin "2") (pinfunction "2_2") (pintype "input"))
      (node (ref "STM32F103CBT6") (pin "6") (pinfunction "PD1-OSC_OUT_6") (pintype "unspecified"))
      (node (ref "X1") (pin "3") (pinfunction "3_3") (pintype "input"))
    )
    (net (code "36") (name "PA1_LED") (class "Default")
      (node (ref "R1") (pin "2") (pinfunction "2_2") (pintype "input"))
      (node (ref "STM32F103CBT6") (pin "11") (pinfunction "PA1_11") (pintype "unspecified"))
    )
    (net (code "37") (name "PB1") (class "Default")
      (node (ref "STM32F103CBT6") (pin "19") (pinfunction "PB1_19") (pintype "unspecified"))
      (node (ref "SW2") (pin "2") (pinfunction "2_2") (pintype "unspecified"))
    )
    (net (code "38") (name "SPI2_MISO") (class "Default")
      (node (ref "FLASH1") (pin "2") (pinfunction "DO/IO1_2") (pintype "unspecified"))
      (node (ref "STM32F103CBT6") (pin "27") (pinfunction "PB14_27") (pintype "unspecified"))
    )
    (net (code "39") (name "SPI2_MOSI") (class "Default")
      (node (ref "FLASH1") (pin "5") (pinfunction "DI/IO0_5") (pintype "unspecified"))
      (node (ref "STM32F103CBT6") (pin "28") (pinfunction "PB15_28") (pintype "unspecified"))
    )
    (net (code "40") (name "SPI2_SCK") (class "Default")
      (node (ref "FLASH1") (pin "6") (pinfunction "CLK_6") (pintype "unspecified"))
      (node (ref "STM32F103CBT6") (pin "26") (pinfunction "PB13_26") (pintype "unspecified"))
    )
    (net (code "41") (name "SYS_JTCK-SWCLK") (class "Default")
      (node (ref "STLink1") (pin "3") (pinfunction "3_3") (pintype "unspecified"))
      (node (ref "STM32F103CBT6") (pin "37") (pinfunction "PA14_37") (pintype "unspecified"))
    )
    (net (code "42") (name "SYS_JTMS-SWDIO") (class "Default")
      (node (ref "STLink1") (pin "4") (pinfunction "4_4") (pintype "unspecified"))
      (node (ref "STM32F103CBT6") (pin "34") (pinfunction "PA13_34") (pintype "unspecified"))
    )
    (net (code "43") (name "USART1_RX") (class "Default")
      (node (ref "HC051") (pin "4") (pinfunction "4_4") (pintype "unspecified"))
      (node (ref "STM32F103CBT6") (pin "31") (pinfunction "PA10_31") (pintype "unspecified"))
    )
    (net (code "44") (name "USART1_TX") (class "Default")
      (node (ref "HC051") (pin "5") (pinfunction "5_5") (pintype "unspecified"))
      (node (ref "STM32F103CBT6") (pin "30") (pinfunction "PA9_30") (pintype "unspecified"))
    )
    (net (code "45") (name "USART3_RX") (class "Default")
      (node (ref "HC052") (pin "4") (pinfunction "4_4") (pintype "unspecified"))
      (node (ref "STM32F103CBT6") (pin "22") (pinfunction "PB11_22") (pintype "unspecified"))
    )
    (net (code "46") (name "USART3_TX") (class "Default")
      (node (ref "HC052") (pin "5") (pinfunction "5_5") (pintype "unspecified"))
      (node (ref "STM32F103CBT6") (pin "21") (pinfunction "PB10_21") (pintype "unspecified"))
    )
    (net (code "47") (name "VBAT_E") (class "Default")
      (node (ref "C1") (pin "2") (pinfunction "2_2") (pintype "unspecified"))
      (node (ref "STM32F103CBT6") (pin "1") (pinfunction "VBAT_1") (pintype "unspecified"))
    )
    (net (code "48") (name "VCC_USB") (class "Default")
      (node (ref "C14") (pin "2") (pinfunction "2_2") (pintype "unspecified"))
      (node (ref "D1") (pin "1") (pinfunction "A_1") (pintype "unspecified"))
      (node (ref "LED3") (pin "2") (pinfunction "A_2") (pintype "input"))
      (node (ref "LED4") (pin "2") (pinfunction "A_2") (pintype "input"))
      (node (ref "Q2") (pin "1") (pinfunction "G_1") (pintype "unspecified"))
      (node (ref "R13") (pin "2") (pinfunction "2_2") (pintype "input"))
      (node (ref "TP4056") (pin "4") (pinfunction "VCC_4") (pintype "unspecified"))
      (node (ref "TP4056") (pin "8") (pinfunction "CE_8") (pintype "unspecified"))
      (node (ref "USB1") (pin "11") (pinfunction "VBUS_11") (pintype "unspecified"))
      (node (ref "USB1") (pin "2") (pinfunction "VBUS_2") (pintype "unspecified"))
    )
    (net (code "49") (name "W25Q16_CHIP_SELECT") (class "Default")
      (node (ref "FLASH1") (pin "1") (pinfunction "/CS_1") (pintype "unspecified"))
      (node (ref "STM32F103CBT6") (pin "25") (pinfunction "PB12_25") (pintype "unspecified"))
    )
    (net (code "50") (name "unconnected-(FLASH1-IO2-Pad3)") (class "Default")
      (node (ref "FLASH1") (pin "3") (pinfunction "IO2_3") (pintype "unspecified+no_connect"))
    )
    (net (code "51") (name "unconnected-(FLASH1-IO3-Pad7)") (class "Default")
      (node (ref "FLASH1") (pin "7") (pinfunction "IO3_7") (pintype "unspecified+no_connect"))
    )
    (net (code "52") (name "unconnected-(HC051-Pad1)") (class "Default")
      (node (ref "HC051") (pin "1") (pinfunction "1_1") (pintype "unspecified+no_connect"))
    )
    (net (code "53") (name "unconnected-(HC051-Pad6)") (class "Default")
      (node (ref "HC051") (pin "6") (pinfunction "6_6") (pintype "unspecified+no_connect"))
    )
    (net (code "54") (name "unconnected-(HC052-Pad1)") (class "Default")
      (node (ref "HC052") (pin "1") (pinfunction "1_1") (pintype "unspecified+no_connect"))
    )
    (net (code "55") (name "unconnected-(HC052-Pad6)") (class "Default")
      (node (ref "HC052") (pin "6") (pinfunction "6_6") (pintype "unspecified+no_connect"))
    )
    (net (code "56") (name "unconnected-(MPU6050-AUX_CL-Pad7)") (class "Default")
      (node (ref "MPU6050") (pin "7") (pinfunction "AUX_CL_7") (pintype "unspecified+no_connect"))
    )
    (net (code "57") (name "unconnected-(MPU6050-AUX_DA-Pad6)") (class "Default")
      (node (ref "MPU6050") (pin "6") (pinfunction "AUX_DA_6") (pintype "unspecified+no_connect"))
    )
    (net (code "58") (name "unconnected-(MPU6050-EP-Pad25)") (class "Default")
      (node (ref "MPU6050") (pin "25") (pinfunction "EP_25") (pintype "unspecified+no_connect"))
    )
    (net (code "59") (name "unconnected-(MPU6050-NC-Pad2)") (class "Default")
      (node (ref "MPU6050") (pin "2") (pinfunction "NC_2") (pintype "unspecified+no_connect"))
    )
    (net (code "60") (name "unconnected-(MPU6050-NC-Pad3)") (class "Default")
      (node (ref "MPU6050") (pin "3") (pinfunction "NC_3") (pintype "unspecified+no_connect"))
    )
    (net (code "61") (name "unconnected-(MPU6050-NC-Pad4)") (class "Default")
      (node (ref "MPU6050") (pin "4") (pinfunction "NC_4") (pintype "unspecified+no_connect"))
    )
    (net (code "62") (name "unconnected-(MPU6050-NC-Pad5)") (class "Default")
      (node (ref "MPU6050") (pin "5") (pinfunction "NC_5") (pintype "unspecified+no_connect"))
    )
    (net (code "63") (name "unconnected-(MPU6050-NC-Pad14)") (class "Default")
      (node (ref "MPU6050") (pin "14") (pinfunction "NC_14") (pintype "unspecified+no_connect"))
    )
    (net (code "64") (name "unconnected-(MPU6050-NC-Pad15)") (class "Default")
      (node (ref "MPU6050") (pin "15") (pinfunction "NC_15") (pintype "unspecified+no_connect"))
    )
    (net (code "65") (name "unconnected-(MPU6050-NC-Pad16)") (class "Default")
      (node (ref "MPU6050") (pin "16") (pinfunction "NC_16") (pintype "unspecified+no_connect"))
    )
    (net (code "66") (name "unconnected-(MPU6050-NC-Pad17)") (class "Default")
      (node (ref "MPU6050") (pin "17") (pinfunction "NC_17") (pintype "unspecified+no_connect"))
    )
    (net (code "67") (name "unconnected-(MPU6050-RESV-Pad19)") (class "Default")
      (node (ref "MPU6050") (pin "19") (pinfunction "RESV_19") (pintype "unspecified+no_connect"))
    )
    (net (code "68") (name "unconnected-(MPU6050-RESV-Pad21)") (class "Default")
      (node (ref "MPU6050") (pin "21") (pinfunction "RESV_21") (pintype "unspecified+no_connect"))
    )
    (net (code "69") (name "unconnected-(MPU6050-RESV-Pad22)") (class "Default")
      (node (ref "MPU6050") (pin "22") (pinfunction "RESV_22") (pintype "unspecified+no_connect"))
    )
    (net (code "70") (name "unconnected-(RT9013-NC-Pad4)") (class "Default")
      (node (ref "RT9013") (pin "4") (pinfunction "NC_4") (pintype "unspecified+no_connect"))
    )
    (net (code "71") (name "unconnected-(STM32F103CBT6-PA2-Pad12)") (class "Default")
      (node (ref "STM32F103CBT6") (pin "12") (pinfunction "PA2_12") (pintype "unspecified"))
    )
    (net (code "72") (name "unconnected-(STM32F103CBT6-PA3-Pad13)") (class "Default")
      (node (ref "STM32F103CBT6") (pin "13") (pinfunction "PA3_13") (pintype "unspecified"))
    )
    (net (code "73") (name "unconnected-(STM32F103CBT6-PA4-Pad14)") (class "Default")
      (node (ref "STM32F103CBT6") (pin "14") (pinfunction "PA4_14") (pintype "unspecified+no_connect"))
    )
    (net (code "74") (name "unconnected-(STM32F103CBT6-PA5-Pad15)") (class "Default")
      (node (ref "STM32F103CBT6") (pin "15") (pinfunction "PA5_15") (pintype "unspecified+no_connect"))
    )
    (net (code "75") (name "unconnected-(STM32F103CBT6-PA6-Pad16)") (class "Default")
      (node (ref "STM32F103CBT6") (pin "16") (pinfunction "PA6_16") (pintype "unspecified+no_connect"))
    )
    (net (code "76") (name "unconnected-(STM32F103CBT6-PA7-Pad17)") (class "Default")
      (node (ref "STM32F103CBT6") (pin "17") (pinfunction "PA7_17") (pintype "unspecified+no_connect"))
    )
    (net (code "77") (name "unconnected-(STM32F103CBT6-PA8-Pad29)") (class "Default")
      (node (ref "STM32F103CBT6") (pin "29") (pinfunction "PA8_29") (pintype "unspecified"))
    )
    (net (code "78") (name "unconnected-(STM32F103CBT6-PA11-Pad32)") (class "Default")
      (node (ref "STM32F103CBT6") (pin "32") (pinfunction "PA11_32") (pintype "unspecified+no_connect"))
    )
    (net (code "79") (name "unconnected-(STM32F103CBT6-PA12-Pad33)") (class "Default")
      (node (ref "STM32F103CBT6") (pin "33") (pinfunction "PA12_33") (pintype "unspecified+no_connect"))
    )
    (net (code "80") (name "unconnected-(STM32F103CBT6-PA15-Pad38)") (class "Default")
      (node (ref "STM32F103CBT6") (pin "38") (pinfunction "PA15_38") (pintype "unspecified+no_connect"))
    )
    (net (code "81") (name "unconnected-(STM32F103CBT6-PB0-Pad18)") (class "Default")
      (node (ref "STM32F103CBT6") (pin "18") (pinfunction "PB0_18") (pintype "unspecified"))
    )
    (net (code "82") (name "unconnected-(STM32F103CBT6-PB2-Pad20)") (class "Default")
      (node (ref "STM32F103CBT6") (pin "20") (pinfunction "PB2_20") (pintype "unspecified+no_connect"))
    )
    (net (code "83") (name "unconnected-(STM32F103CBT6-PB3-Pad39)") (class "Default")
      (node (ref "STM32F103CBT6") (pin "39") (pinfunction "PB3_39") (pintype "unspecified+no_connect"))
    )
    (net (code "84") (name "unconnected-(STM32F103CBT6-PB5-Pad41)") (class "Default")
      (node (ref "STM32F103CBT6") (pin "41") (pinfunction "PB5_41") (pintype "unspecified+no_connect"))
    )
    (net (code "85") (name "unconnected-(STM32F103CBT6-PB6-Pad42)") (class "Default")
      (node (ref "STM32F103CBT6") (pin "42") (pinfunction "PB6_42") (pintype "unspecified+no_connect"))
    )
    (net (code "86") (name "unconnected-(STM32F103CBT6-PB7-Pad43)") (class "Default")
      (node (ref "STM32F103CBT6") (pin "43") (pinfunction "PB7_43") (pintype "unspecified+no_connect"))
    )
    (net (code "87") (name "unconnected-(STM32F103CBT6-PC13-TAMPER-RTC-Pad2)") (class "Default")
      (node (ref "STM32F103CBT6") (pin "2") (pinfunction "PC13-TAMPER-RTC_2") (pintype "unspecified+no_connect"))
    )
    (net (code "88") (name "unconnected-(STM32F103CBT6-PC14-OSC32_IN-Pad3)") (class "Default")
      (node (ref "STM32F103CBT6") (pin "3") (pinfunction "PC14-OSC32_IN_3") (pintype "unspecified+no_connect"))
    )
    (net (code "89") (name "unconnected-(STM32F103CBT6-PC15-OSC32_OUT-Pad4)") (class "Default")
      (node (ref "STM32F103CBT6") (pin "4") (pinfunction "PC15-OSC32_OUT_4") (pintype "unspecified+no_connect"))
    )
    (net (code "90") (name "unconnected-(SW1-Pad3)") (class "Default")
      (node (ref "SW1") (pin "3") (pinfunction "3_3") (pintype "unspecified+no_connect"))
    )
    (net (code "91") (name "unconnected-(SW2-Pad3)") (class "Default")
      (node (ref "SW2") (pin "3") (pinfunction "3_3") (pintype "unspecified+no_connect"))
    )
    (net (code "92") (name "unconnected-(USB1-DN1-Pad7)") (class "Default")
      (node (ref "USB1") (pin "7") (pinfunction "DN1_7") (pintype "unspecified+no_connect"))
    )
    (net (code "93") (name "unconnected-(USB1-DN2-Pad5)") (class "Default")
      (node (ref "USB1") (pin "5") (pinfunction "DN2_5") (pintype "unspecified+no_connect"))
    )
    (net (code "94") (name "unconnected-(USB1-DP1-Pad6)") (class "Default")
      (node (ref "USB1") (pin "6") (pinfunction "DP1_6") (pintype "unspecified+no_connect"))
    )
    (net (code "95") (name "unconnected-(USB1-DP2-Pad8)") (class "Default")
      (node (ref "USB1") (pin "8") (pinfunction "DP2_8") (pintype "unspecified+no_connect"))
    )
    (net (code "96") (name "unconnected-(USB1-SBU1-Pad9)") (class "Default")
      (node (ref "USB1") (pin "9") (pinfunction "SBU1_9") (pintype "unspecified+no_connect"))
    )
    (net (code "97") (name "unconnected-(USB1-SBU2-Pad3)") (class "Default")
      (node (ref "USB1") (pin "3") (pinfunction "SBU2_3") (pintype "unspecified+no_connect"))
    )
  )
)
